# A1_0-_-1_1-DC-DC12V_5V_3_3V-24_10_16.net
KiCad netlist of a schematic drawn in Altium Designer
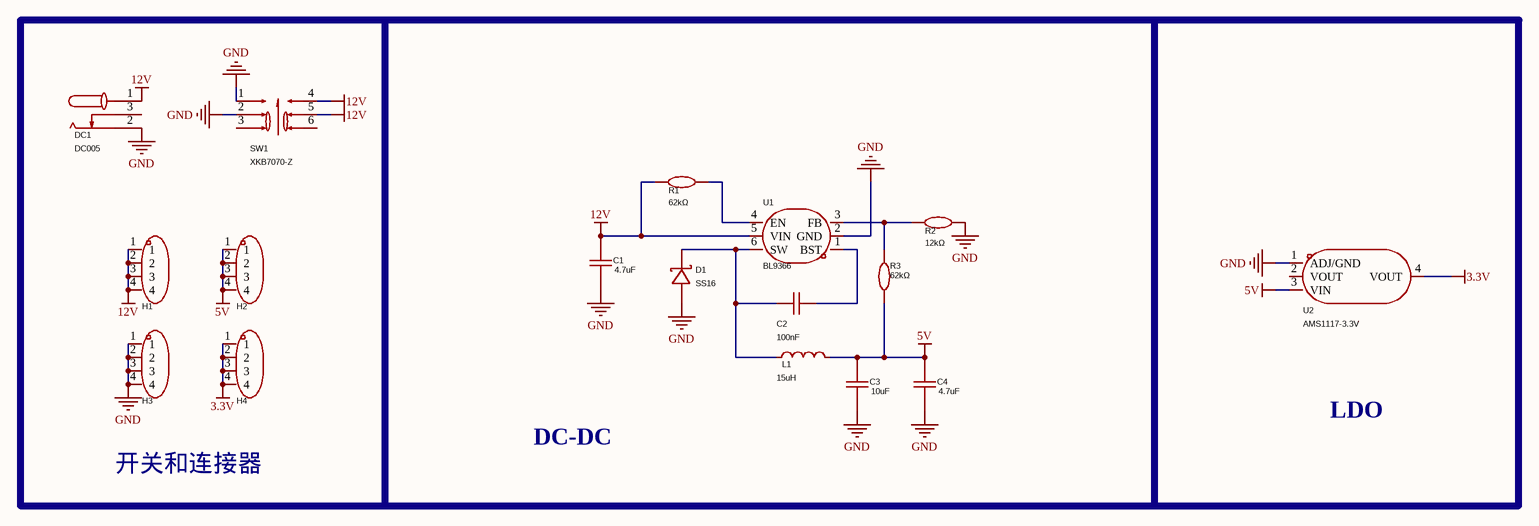
[diagram p0: A1.0-电源-1.1-DC-DC12V输入转5V和3.3V-24.10.16.SchDoc]

(export (version "E")
  (design (tool "Eeschema 10.0.6"))
  (components
    (comp (ref "C1")
      (value "4.7uF")
      (footprint "C0603")
      (fields
        (field (name "MANUFACTURER") "FH(风华)")
        (field (name "MANUFACTURER PART") "0603X475K250NT")
        (field (name "TOLERANCE") "±10%")
      )
      (libsource (lib "电容") (part "0603X475K250NT"))
    )
    (comp (ref "C2")
      (value "100nF")
      (footprint "C0603")
      (fields
        (field (name "MANUFACTURER") "FH(风华)")
        (field (name "MANUFACTURER PART") "0603B104K500NT")
        (field (name "TOLERANCE") "±10%")
      )
      (libsource (lib "电容") (part "0603B104K500NT"))
    )
    (comp (ref "C3")
      (value "10uF")
      (footprint "C0603")
      (fields
        (field (name "MANUFACTURER") "FH(风华)")
        (field (name "MANUFACTURER PART") "0603X106M250NT")
        (field (name "TOLERANCE") "±20%")
      )
      (libsource (lib "电容") (part "0603X106M250NT"))
    )
    (comp (ref "C4")
      (value "4.7uF")
      (footprint "C0603")
      (fields
        (field (name "MANUFACTURER") "FH(风华)")
        (field (name "MANUFACTURER PART") "0603X475K250NT")
        (field (name "TOLERANCE") "±10%")
      )
      (libsource (lib "电容") (part "0603X475K250NT"))
    )
    (comp (ref "D1")
      (value "SS16")
      (footprint "SMA_L4.3-W2.6-LS5.2-RD")
      (fields (field (name "MANUFACTURER") "MDD(辰达半导体)"))
      (libsource (lib "二极管") (part "SS16_C2481"))
    )
    (comp (ref "DC1")
      (value "DC005")
      (footprint "DC-IN-TH_DC005")
      (fields (field (name "MANUFACTURER") "SHOU HAN(首韩)"))
      (libsource (lib "连接器") (part "DC005"))
    )
    (comp (ref "H1")
      (value "PZ254V-11-04P")
      (footprint "HDR-TH_4P-P2.54-V-M")
      (fields (field (name "MANUFACTURER") "XFCN(兴飞)"))
      (libsource (lib "连接器") (part "PZ254V-11-04P"))
    )
    (comp (ref "H2")
      (value "PZ254V-11-04P")
      (footprint "HDR-TH_4P-P2.54-V-M")
      (fields (field (name "MANUFACTURER") "XFCN(兴飞)"))
      (libsource (lib "连接器") (part "PZ254V-11-04P"))
    )
    (comp (ref "H3")
      (value "PZ254V-11-04P")
      (footprint "HDR-TH_4P-P2.54-V-M")
      (fields (field (name "MANUFACTURER") "XFCN(兴飞)"))
      (libsource (lib "连接器") (part "PZ254V-11-04P"))
    )
    (comp (ref "H4")
      (value "PZ254V-11-04P")
      (footprint "HDR-TH_4P-P2.54-V-M")
      (fields (field (name "MANUFACTURER") "XFCN(兴飞)"))
      (libsource (lib "连接器") (part "PZ254V-11-04P"))
    )
    (comp (ref "L1")
      (value "15uH")
      (footprint "IND-SMD_L11.5-W10.0_FXL1040")
      (fields
        (field (name "MANUFACTURER") "cjiang(长江微电)")
        (field (name "MANUFACTURER PART") "FXL1040-150-M")
        (field (name "TOLERANCE") "±20%")
      )
      (libsource (lib "电感") (part "FXL1040-150-M"))
    )
    (comp (ref "R1")
      (value "62kΩ")
      (footprint "R0603")
      (fields
        (field (name "MANUFACTURER") "UNI-ROYAL(厚声)")
        (field (name "MANUFACTURER PART") "0603WAF6202T5E")
        (field (name "TOLERANCE") "±1%")
      )
      (libsource (lib "电阻") (part "0603WAF6202T5E"))
    )
    (comp (ref "R2")
      (value "12kΩ")
      (footprint "R0603")
      (fields
        (field (name "MANUFACTURER") "UNI-ROYAL(厚声)")
        (field (name "MANUFACTURER PART") "0603WAF1202T5E")
        (field (name "TOLERANCE") "±1%")
      )
      (libsource (lib "电阻") (part "0603WAF1202T5E"))
    )
    (comp (ref "R3")
      (value "62kΩ")
      (footprint "R0603")
      (fields
        (field (name "MANUFACTURER") "UNI-ROYAL(厚声)")
        (field (name "MANUFACTURER PART") "0603WAF6202T5E")
        (field (name "TOLERANCE") "±1%")
      )
      (libsource (lib "电阻") (part "0603WAF6202T5E"))
    )
    (comp (ref "SW1")
      (value "XKB7070-Z")
      (footprint "SW-TH_6P-L7.0-W7.0-P2.00")
      (fields (field (name "MANUFACTURER") "XKB Connectivity(中国星坤)"))
      (libsource (lib "开关") (part "XKB7070-Z"))
    )
    (comp (ref "U1")
      (value "BL9366")
      (footprint "SOT-23-6_L2.9-W1.6-P0.95-LS2.8-BR")
      (fields (field (name "MANUFACTURER") "BL(上海贝岭)"))
      (libsource (lib "电源器件") (part "BL9366"))
    )
    (comp (ref "U2")
      (value "AMS1117-3.3V")
      (footprint "SOT-223-4_L6.5-W3.5-P2.30-LS7.0-TR")
      (fields (field (name "MANUFACTURER") "MSKSEMI(美森科)"))
      (libsource (lib "电源器件") (part "AMS1117-3.3V_C5120765"))
    )
  )
  (nets
    (net (code "1") (name "3.3V") (class "Default")
      (node (ref "H4") (pin "1") (pinfunction "1_1") (pintype "passive"))
      (node (ref "H4") (pin "2") (pinfunction "2_2") (pintype "passive"))
      (node (ref "H4") (pin "3") (pinfunction "3_3") (pintype "passive"))
      (node (ref "H4") (pin "4") (pinfunction "4_4") (pintype "passive"))
      (node (ref "U2") (pin "4") (pinfunction "VOUT_4") (pintype "passive"))
    )
    (net (code "2") (name "5V") (class "Default")
      (node (ref "C3") (pin "2") (pinfunction "2_2") (pintype "passive"))
      (node (ref "C4") (pin "2") (pinfunction "2_2") (pintype "passive"))
      (node (ref "H2") (pin "1") (pinfunction "1_1") (pintype "passive"))
      (node (ref "H2") (pin "2") (pinfunction "2_2") (pintype "passive"))
      (node (ref "H2") (pin "3") (pinfunction "3_3") (pintype "passive"))
      (node (ref "H2") (pin "4") (pinfunction "4_4") (pintype "passive"))
      (node (ref "L1") (pin "2") (pinfunction "2_2") (pintype "passive"))
      (node (ref "R3") (pin "1") (pinfunction "1_1") (pintype "passive"))
      (node (ref "U2") (pin "3") (pinfunction "VIN_3") (pintype "passive"))
    )
    (net (code "3") (name "12V") (class "Default")
      (node (ref "C1") (pin "2") (pinfunction "2_2") (pintype "passive"))
      (node (ref "DC1") (pin "1") (pinfunction "1_1") (pintype "passive"))
      (node (ref "H1") (pin "1") (pinfunction "1_1") (pintype "passive"))
      (node (ref "H1") (pin "2") (pinfunction "2_2") (pintype "passive"))
      (node (ref "H1") (pin "3") (pinfunction "3_3") (pintype "passive"))
      (node (ref "H1") (pin "4") (pinfunction "4_4") (pintype "passive"))
      (node (ref "R1") (pin "1") (pinfunction "1_1") (pintype "passive"))
      (node (ref "SW1") (pin "4") (pinfunction "4_4") (pintype "passive"))
      (node (ref "SW1") (pin "5") (pinfunction "5_5") (pintype "passive"))
      (node (ref "U1") (pin "5") (pinfunction "VIN_5") (pintype "passive"))
    )
    (net (code "4") (name "GND") (class "Default")
      (node (ref "C1") (pin "1") (pinfunction "1_1") (pintype "passive"))
      (node (ref "C3") (pin "1") (pinfunction "1_1") (pintype "passive"))
      (node (ref "C4") (pin "1") (pinfunction "1_1") (pintype "passive"))
      (node (ref "D1") (pin "2") (pinfunction "A_2") (pintype "passive"))
      (node (ref "DC1") (pin "2") (pinfunction "2_2") (pintype "passive"))
      (node (ref "H3") (pin "1") (pinfunction "1_1") (pintype "passive"))
      (node (ref "H3") (pin "2") (pinfunction "2_2") (pintype "passive"))
      (node (ref "H3") (pin "3") (pinfunction "3_3") (pintype "passive"))
      (node (ref "H3") (pin "4") (pinfunction "4_4") (pintype "passive"))
      (node (ref "R2") (pin "2") (pinfunction "2_2") (pintype "passive"))
      (node (ref "SW1") (pin "1") (pinfunction "1_1") (pintype "passive"))
      (node (ref "SW1") (pin "2") (pinfunction "2_2") (pintype "passive"))
      (node (ref "U1") (pin "2") (pinfunction "GND_2") (pintype "passive"))
      (node (ref "U2") (pin "1") (pinfunction "ADJ/GND_1") (pintype "passive"))
    )
    (net (code "5") (name "Net-(D1-K)") (class "Default")
      (node (ref "C2") (pin "1") (pinfunction "1_1") (pintype "passive"))
      (node (ref "D1") (pin "1") (pinfunction "K_1") (pintype "passive"))
      (node (ref "L1") (pin "1") (pinfunction "1_1") (pintype "passive"))
      (node (ref "U1") (pin "6") (pinfunction "SW_6") (pintype "passive"))
    )
    (net (code "6") (name "Net-(U1-BST)") (class "Default")
      (node (ref "C2") (pin "2") (pinfunction "2_2") (pintype "passive"))
      (node (ref "U1") (pin "1") (pinfunction "BST_1") (pintype "passive"))
    )
    (net (code "7") (name "Net-(U1-EN)") (class "Default")
      (node (ref "R1") (pin "2") (pinfunction "2_2") (pintype "passive"))
      (node (ref "U1") (pin "4") (pinfunction "EN_4") (pintype "passive"))
    )
    (net (code "8") (name "Net-(U1-FB)") (class "Default")
      (node (ref "R2") (pin "1") (pinfunction "1_1") (pintype "passive"))
      (node (ref "R3") (pin "2") (pinfunction "2_2") (pintype "passive"))
      (node (ref "U1") (pin "3") (pinfunction "FB_3") (pintype "passive"))
    )
    (net (code "9") (name "unconnected-(DC1-Pad3)") (class "Default")
      (node (ref "DC1") (pin "3") (pinfunction "3_3") (pintype "passive"))
    )
    (net (code "10") (name "unconnected-(SW1-Pad3)") (class "Default")
      (node (ref "SW1") (pin "3") (pinfunction "3_3") (pintype "passive"))
    )
    (net (code "11") (name "unconnected-(SW1-Pad6)") (class "Default")
      (node (ref "SW1") (pin "6") (pinfunction "6_6") (pintype "passive"))
    )
    (net (code "12") (name "unconnected-(U2-VOUT-Pad2)") (class "Default")
      (node (ref "U2") (pin "2") (pinfunction "VOUT_2") (pintype "passive"))
    )
  )
)
